# Rfid.net
KiCad netlist of a schematic drawn in EAGLE
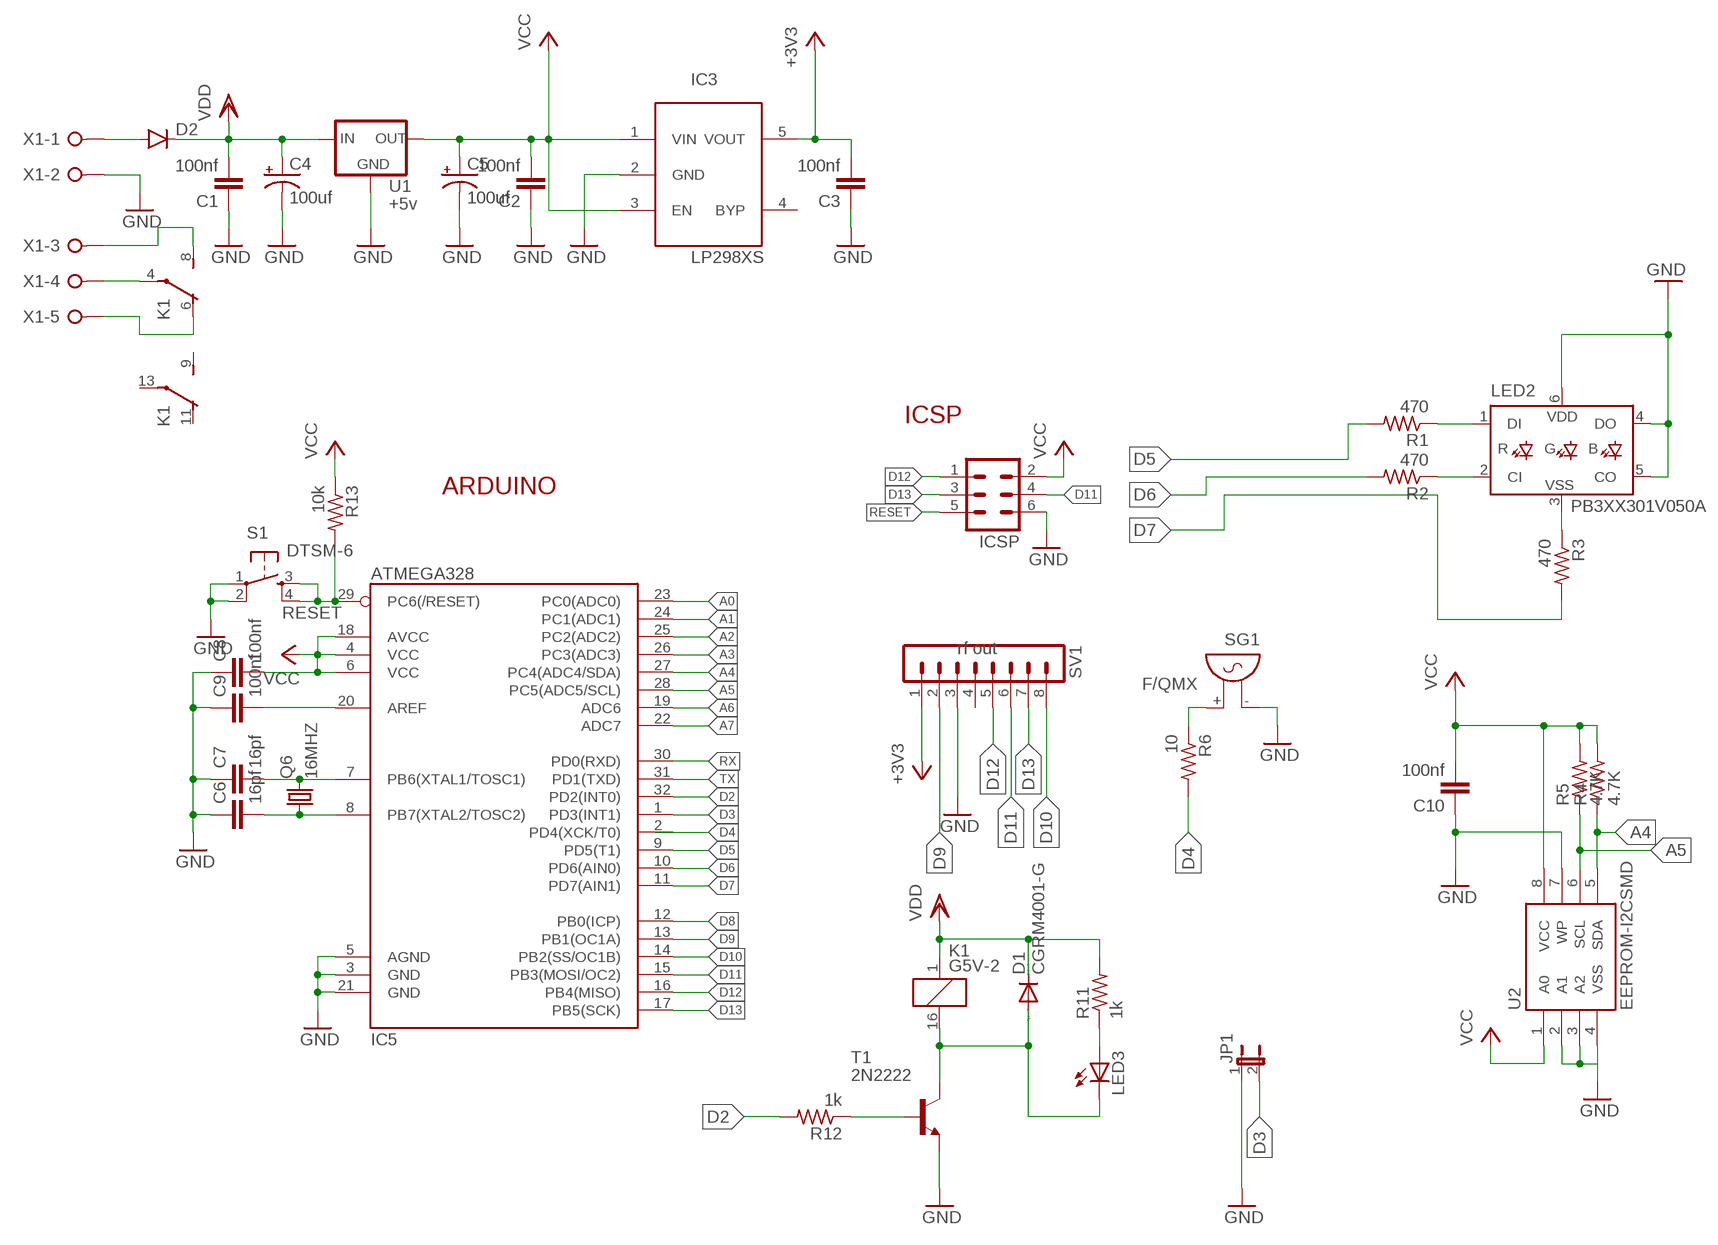
[diagram p0: schematic, sheet 1]

(export (version "E")
  (design (tool "Eeschema 10.0.6"))
  (components
    (comp (ref "C1")
      (value "100nf")
      (footprint "eagle-import:C0805")
      (libsource (lib "eagle-import") (part "C-EUC0805"))
    )
    (comp (ref "C2")
      (value "100nf")
      (footprint "eagle-import:C0805")
      (libsource (lib "eagle-import") (part "C-EUC0805"))
    )
    (comp (ref "C3")
      (value "100nf")
      (footprint "eagle-import:C0805")
      (libsource (lib "eagle-import") (part "C-EUC0805"))
    )
    (comp (ref "C4")
      (value "100uf")
      (footprint "eagle-import:PANASONIC_D")
      (libsource (lib "eagle-import") (part "CAP_POLD"))
    )
    (comp (ref "C5")
      (value "100uf")
      (footprint "eagle-import:PANASONIC_D")
      (libsource (lib "eagle-import") (part "CAP_POLD"))
    )
    (comp (ref "C6")
      (value "16pf")
      (footprint "eagle-import:C0805")
      (libsource (lib "eagle-import") (part "C-EUC0805"))
    )
    (comp (ref "C7")
      (value "16pf")
      (footprint "eagle-import:C0805")
      (libsource (lib "eagle-import") (part "C-EUC0805"))
    )
    (comp (ref "C8")
      (value "100nf")
      (footprint "eagle-import:C0805")
      (libsource (lib "eagle-import") (part "C-EUC0805"))
    )
    (comp (ref "C9")
      (value "100nf")
      (footprint "eagle-import:C0805")
      (libsource (lib "eagle-import") (part "C-EUC0805"))
    )
    (comp (ref "C10")
      (value "100nf")
      (footprint "eagle-import:C0805")
      (libsource (lib "eagle-import") (part "C-EUC0805"))
    )
    (comp (ref "D1")
      (value "CGRM4001-G")
      (footprint "eagle-import:SOD-123_MINI-SMA")
      (libsource (lib "eagle-import") (part "CGRM400-G1"))
    )
    (comp (ref "D2")
      (value "DIODESMA-ALT")
      (footprint "eagle-import:SMA-DIODE_ALT")
      (libsource (lib "eagle-import") (part "DIODESMA-ALT"))
    )
    (comp (ref "IC3")
      (value "LP298XS")
      (footprint "eagle-import:SOT23-5L")
      (libsource (lib "eagle-import") (part "LP298XS"))
    )
    (comp (ref "IC5")
      (value "ATMEGA328")
      (footprint "eagle-import:TQFP32-08")
      (libsource (lib "eagle-import") (part "ATMEGA168"))
    )
    (comp (ref "ICSP")
      (value "ML6")
      (footprint "eagle-import:ML6")
      (libsource (lib "eagle-import") (part "ML6"))
    )
    (comp (ref "JP1")
      (value "JUMPER-2PTH")
      (footprint "eagle-import:1X02")
      (libsource (lib "eagle-import") (part "JUMPER-2PTH"))
    )
    (comp (ref "K1")
      (value "G5V-2")
      (footprint "eagle-import:G5V-2")
      (fields (field (name "MPN") "G5V-2 5DC"))
      (libsource (lib "eagle-import") (part "G5V-2"))
    )
    (comp (ref "LED2")
      (value "PB3XX301V050A")
      (footprint "eagle-import:PB3XX301V050A")
      (libsource (lib "eagle-import") (part "PB3XX301V050A"))
    )
    (comp (ref "LED3")
      (value "LEDCHIPLED_0805")
      (footprint "eagle-import:CHIPLED_0805")
      (libsource (lib "eagle-import") (part "LEDCHIPLED_0805"))
    )
    (comp (ref "Q6")
      (value "16MHZ")
      (footprint "eagle-import:HC49_S")
      (libsource (lib "eagle-import") (part "CRYSTALHC49S"))
    )
    (comp (ref "R1")
      (value "470")
      (footprint "eagle-import:R0805")
      (libsource (lib "eagle-import") (part "R-US_R0805"))
    )
    (comp (ref "R2")
      (value "470")
      (footprint "eagle-import:R0805")
      (libsource (lib "eagle-import") (part "R-US_R0805"))
    )
    (comp (ref "R3")
      (value "470")
      (footprint "eagle-import:R0805")
      (libsource (lib "eagle-import") (part "R-US_R0805"))
    )
    (comp (ref "R4")
      (value "4.7K")
      (footprint "eagle-import:R0805")
      (libsource (lib "eagle-import") (part "R-US_R0805"))
    )
    (comp (ref "R5")
      (value "4.7K")
      (footprint "eagle-import:R0805")
      (libsource (lib "eagle-import") (part "R-US_R0805"))
    )
    (comp (ref "R6")
      (value "10")
      (footprint "eagle-import:R0805")
      (libsource (lib "eagle-import") (part "R-US_R0805"))
    )
    (comp (ref "R11")
      (value "1k")
      (footprint "eagle-import:R0805")
      (libsource (lib "eagle-import") (part "R-US_R0805"))
    )
    (comp (ref "R12")
      (value "1k")
      (footprint "eagle-import:R0805")
      (libsource (lib "eagle-import") (part "R-US_R0805"))
    )
    (comp (ref "R13")
      (value "10k")
      (footprint "eagle-import:R0805")
      (libsource (lib "eagle-import") (part "R-US_R0805"))
    )
    (comp (ref "S1")
      (value "DTSM-6")
      (footprint "eagle-import:DTSM-6")
      (libsource (lib "eagle-import") (part "DTSM-6"))
    )
    (comp (ref "SG1")
      (value "F/QMX")
      (footprint "eagle-import:F_QMX")
      (libsource (lib "eagle-import") (part "F/QMX"))
    )
    (comp (ref "SV1")
      (value "MA08-1")
      (footprint "eagle-import:MA08-1")
      (libsource (lib "eagle-import") (part "MA08-1"))
    )
    (comp (ref "T1")
      (value "2N2222")
      (footprint "eagle-import:SOT23-BEC")
      (libsource (lib "eagle-import") (part "-NPN-SOT23-BECMMBT2222ALT1"))
    )
    (comp (ref "U1")
      (value "+5v")
      (footprint "eagle-import:TO-252")
      (libsource (lib "eagle-import") (part "V_REG_78XX7812"))
    )
    (comp (ref "U2")
      (value "EEPROM-I2CSMD")
      (footprint "eagle-import:SO08")
      (libsource (lib "eagle-import") (part "EEPROM-I2CSMD"))
    )
    (comp (ref "X1")
      (value "W237-05P")
      (footprint "eagle-import:W237-5P")
      (libsource (lib "eagle-import") (part "W237-05P"))
    )
  )
  (nets
    (net (code "1") (name "+3V3") (class "Default")
      (node (ref "C3") (pin "2") (pinfunction "2_2") (pintype "passive"))
      (node (ref "IC3") (pin "5") (pinfunction "VOUT_5") (pintype "bidirectional"))
      (node (ref "SV1") (pin "1") (pinfunction "1_1") (pintype "passive"))
    )
    (net (code "2") (name "A0") (class "Default")
      (node (ref "IC5") (pin "23") (pinfunction "PC0(ADC0)_23") (pintype "bidirectional"))
    )
    (net (code "3") (name "A1") (class "Default")
      (node (ref "IC5") (pin "24") (pinfunction "PC1(ADC1)_24") (pintype "bidirectional"))
    )
    (net (code "4") (name "A2") (class "Default")
      (node (ref "IC5") (pin "25") (pinfunction "PC2(ADC2)_25") (pintype "bidirectional"))
    )
    (net (code "5") (name "A3") (class "Default")
      (node (ref "IC5") (pin "26") (pinfunction "PC3(ADC3)_26") (pintype "bidirectional"))
    )
    (net (code "6") (name "A4") (class "Default")
      (node (ref "IC5") (pin "27") (pinfunction "PC4(ADC4/SDA)_27") (pintype "bidirectional"))
      (node (ref "R4") (pin "1") (pinfunction "1_1") (pintype "passive"))
      (node (ref "U2") (pin "5") (pinfunction "SDA_5") (pintype "bidirectional"))
    )
    (net (code "7") (name "A5") (class "Default")
      (node (ref "IC5") (pin "28") (pinfunction "PC5(ADC5/SCL)_28") (pintype "bidirectional"))
      (node (ref "R5") (pin "1") (pinfunction "1_1") (pintype "passive"))
      (node (ref "U2") (pin "6") (pinfunction "SCL_6") (pintype "bidirectional"))
    )
    (net (code "8") (name "A6") (class "Default")
      (node (ref "IC5") (pin "19") (pinfunction "ADC6_19") (pintype "bidirectional"))
    )
    (net (code "9") (name "A7") (class "Default")
      (node (ref "IC5") (pin "22") (pinfunction "ADC7_22") (pintype "bidirectional"))
    )
    (net (code "10") (name "D2") (class "Default")
      (node (ref "IC5") (pin "32") (pinfunction "PD2(INT0)_32") (pintype "bidirectional"))
      (node (ref "R12") (pin "2") (pinfunction "2_2") (pintype "passive"))
    )
    (net (code "11") (name "D3") (class "Default")
      (node (ref "IC5") (pin "1") (pinfunction "PD3(INT1)_1") (pintype "bidirectional"))
      (node (ref "JP1") (pin "2") (pinfunction "2_2") (pintype "passive"))
    )
    (net (code "12") (name "D4") (class "Default")
      (node (ref "IC5") (pin "2") (pinfunction "PD4(XCK/T0)_2") (pintype "bidirectional"))
      (node (ref "R6") (pin "2") (pinfunction "2_2") (pintype "passive"))
    )
    (net (code "13") (name "D5") (class "Default")
      (node (ref "IC5") (pin "9") (pinfunction "PD5(T1)_9") (pintype "bidirectional"))
      (node (ref "R1") (pin "2") (pinfunction "2_2") (pintype "passive"))
    )
    (net (code "14") (name "D6") (class "Default")
      (node (ref "IC5") (pin "10") (pinfunction "PD6(AIN0)_10") (pintype "bidirectional"))
      (node (ref "R2") (pin "2") (pinfunction "2_2") (pintype "passive"))
    )
    (net (code "15") (name "D7") (class "Default")
      (node (ref "IC5") (pin "11") (pinfunction "PD7(AIN1)_11") (pintype "bidirectional"))
      (node (ref "R3") (pin "2") (pinfunction "2_2") (pintype "passive"))
    )
    (net (code "16") (name "D8") (class "Default")
      (node (ref "IC5") (pin "12") (pinfunction "PB0(ICP)_12") (pintype "bidirectional"))
    )
    (net (code "17") (name "D9") (class "Default")
      (node (ref "IC5") (pin "13") (pinfunction "PB1(OC1A)_13") (pintype "bidirectional"))
      (node (ref "SV1") (pin "2") (pinfunction "2_2") (pintype "passive"))
    )
    (net (code "18") (name "D10") (class "Default")
      (node (ref "IC5") (pin "14") (pinfunction "PB2(SS/OC1B)_14") (pintype "bidirectional"))
      (node (ref "SV1") (pin "8") (pinfunction "8_8") (pintype "passive"))
    )
    (net (code "19") (name "D11") (class "Default")
      (node (ref "IC5") (pin "15") (pinfunction "PB3(MOSI/OC2)_15") (pintype "bidirectional"))
      (node (ref "ICSP") (pin "4") (pinfunction "4_4") (pintype "passive"))
      (node (ref "SV1") (pin "6") (pinfunction "6_6") (pintype "passive"))
    )
    (net (code "20") (name "D12") (class "Default")
      (node (ref "IC5") (pin "16") (pinfunction "PB4(MISO)_16") (pintype "bidirectional"))
      (node (ref "ICSP") (pin "1") (pinfunction "1_1") (pintype "passive"))
      (node (ref "SV1") (pin "5") (pinfunction "5_5") (pintype "passive"))
    )
    (net (code "21") (name "D13") (class "Default")
      (node (ref "IC5") (pin "17") (pinfunction "PB5(SCK)_17") (pintype "bidirectional"))
      (node (ref "ICSP") (pin "3") (pinfunction "3_3") (pintype "passive"))
      (node (ref "SV1") (pin "7") (pinfunction "7_7") (pintype "passive"))
    )
    (net (code "22") (name "GND") (class "Default")
      (node (ref "C1") (pin "1") (pinfunction "1_1") (pintype "passive"))
      (node (ref "C10") (pin "1") (pinfunction "1_1") (pintype "passive"))
      (node (ref "C2") (pin "1") (pinfunction "1_1") (pintype "passive"))
      (node (ref "C3") (pin "1") (pinfunction "1_1") (pintype "passive"))
      (node (ref "C4") (pin "-") (pinfunction "-_-") (pintype "passive"))
      (node (ref "C5") (pin "-") (pinfunction "-_-") (pintype "passive"))
      (node (ref "C6") (pin "1") (pinfunction "1_1") (pintype "passive"))
      (node (ref "C7") (pin "1") (pinfunction "1_1") (pintype "passive"))
      (node (ref "C8") (pin "1") (pinfunction "1_1") (pintype "passive"))
      (node (ref "C9") (pin "1") (pinfunction "1_1") (pintype "passive"))
      (node (ref "IC3") (pin "2") (pinfunction "GND_2") (pintype "bidirectional"))
      (node (ref "IC5") (pin "21") (pinfunction "GND_21") (pintype "bidirectional"))
      (node (ref "IC5") (pin "3") (pinfunction "GND_3") (pintype "bidirectional"))
      (node (ref "IC5") (pin "5") (pinfunction "AGND_5") (pintype "bidirectional"))
      (node (ref "ICSP") (pin "6") (pinfunction "6_6") (pintype "passive"))
      (node (ref "JP1") (pin "1") (pinfunction "1_1") (pintype "passive"))
      (node (ref "LED2") (pin "4") (pinfunction "DO_4") (pintype "output"))
      (node (ref "LED2") (pin "5") (pinfunction "CO_5") (pintype "output"))
      (node (ref "LED2") (pin "6") (pinfunction "VDD_6") (pintype "power_in"))
      (node (ref "S1") (pin "1") (pinfunction "1_1") (pintype "passive"))
      (node (ref "S1") (pin "2") (pinfunction "2_2") (pintype "passive"))
      (node (ref "SG1") (pin "-") (pinfunction "1_-") (pintype "passive"))
      (node (ref "SV1") (pin "3") (pinfunction "3_3") (pintype "passive"))
      (node (ref "T1") (pin "E") (pinfunction "E_E") (pintype "passive"))
      (node (ref "U1") (pin "3") (pinfunction "GND_3") (pintype "input"))
      (node (ref "U2") (pin "2") (pinfunction "A1_2") (pintype "bidirectional"))
      (node (ref "U2") (pin "3") (pinfunction "A2_3") (pintype "bidirectional"))
      (node (ref "U2") (pin "4") (pinfunction "VSS_4") (pintype "power_in"))
      (node (ref "U2") (pin "7") (pinfunction "WP_7") (pintype "bidirectional"))
      (node (ref "X1") (pin "2") (pinfunction "KL_2") (pintype "passive"))
    )
    (net (code "23") (name "Net-(IC5-AREF)") (class "Default")
      (node (ref "C9") (pin "2") (pinfunction "2_2") (pintype "passive"))
      (node (ref "IC5") (pin "20") (pinfunction "AREF_20") (pintype "bidirectional"))
    )
    (net (code "24") (name "Net-(IC5-PB6(XTAL1{slash}TOSC1))") (class "Default")
      (node (ref "C7") (pin "2") (pinfunction "2_2") (pintype "passive"))
      (node (ref "IC5") (pin "7") (pinfunction "PB6(XTAL1/TOSC1)_7") (pintype "bidirectional"))
      (node (ref "Q6") (pin "2") (pinfunction "2_2") (pintype "passive"))
    )
    (net (code "25") (name "Net-(IC5-PB7(XTAL2{slash}TOSC2))") (class "Default")
      (node (ref "C6") (pin "2") (pinfunction "2_2") (pintype "passive"))
      (node (ref "IC5") (pin "8") (pinfunction "PB7(XTAL2/TOSC2)_8") (pintype "bidirectional"))
      (node (ref "Q6") (pin "1") (pinfunction "1_1") (pintype "passive"))
    )
    (net (code "26") (name "Net-(K1A-O)") (class "Default")
      (node (ref "K1") (pin "6") (pinfunction "O_6") (pintype "passive"))
      (node (ref "X1") (pin "5") (pinfunction "KL_5") (pintype "passive"))
    )
    (net (code "27") (name "Net-(K1A-P)") (class "Default")
      (node (ref "K1") (pin "4") (pinfunction "P_4") (pintype "passive"))
      (node (ref "X1") (pin "4") (pinfunction "KL_4") (pintype "passive"))
    )
    (net (code "28") (name "Net-(K1A-S)") (class "Default")
      (node (ref "K1") (pin "8") (pinfunction "S_8") (pintype "passive"))
      (node (ref "X1") (pin "3") (pinfunction "KL_3") (pintype "passive"))
    )
    (net (code "29") (name "Net-(K1C-2)") (class "Default")
      (node (ref "D1") (pin "A") (pinfunction "A_A") (pintype "passive"))
      (node (ref "K1") (pin "16") (pinfunction "2_16") (pintype "passive"))
      (node (ref "LED3") (pin "C") (pinfunction "C_C") (pintype "passive"))
      (node (ref "T1") (pin "C") (pinfunction "C_C") (pintype "passive"))
    )
    (net (code "30") (name "Net-(LED2-CI)") (class "Default")
      (node (ref "LED2") (pin "2") (pinfunction "CI_2") (pintype "input"))
      (node (ref "R2") (pin "1") (pinfunction "1_1") (pintype "passive"))
    )
    (net (code "31") (name "Net-(LED2-DI)") (class "Default")
      (node (ref "LED2") (pin "1") (pinfunction "DI_1") (pintype "input"))
      (node (ref "R1") (pin "1") (pinfunction "1_1") (pintype "passive"))
    )
    (net (code "32") (name "Net-(LED2-VSS)") (class "Default")
      (node (ref "LED2") (pin "3") (pinfunction "VSS_3") (pintype "power_in"))
      (node (ref "R3") (pin "1") (pinfunction "1_1") (pintype "passive"))
    )
    (net (code "33") (name "Net-(LED3-PadA)") (class "Default")
      (node (ref "LED3") (pin "A") (pinfunction "A_A") (pintype "passive"))
      (node (ref "R11") (pin "1") (pinfunction "1_1") (pintype "passive"))
    )
    (net (code "34") (name "Net-(R12-Pad1)") (class "Default")
      (node (ref "R12") (pin "1") (pinfunction "1_1") (pintype "passive"))
      (node (ref "T1") (pin "B") (pinfunction "B_B") (pintype "passive"))
    )
    (net (code "35") (name "Net-(SG1-2)") (class "Default")
      (node (ref "R6") (pin "1") (pinfunction "1_1") (pintype "passive"))
      (node (ref "SG1") (pin "+") (pinfunction "2_+") (pintype "passive"))
    )
    (net (code "36") (name "Net-(X1A-KL)") (class "Default")
      (node (ref "D2") (pin "A") (pinfunction "A_A") (pintype "passive"))
      (node (ref "X1") (pin "1") (pinfunction "KL_1") (pintype "passive"))
    )
    (net (code "37") (name "RESET") (class "Default")
      (node (ref "IC5") (pin "29") (pinfunction "PC6(/RESET)_29") (pintype "bidirectional"))
      (node (ref "ICSP") (pin "5") (pinfunction "5_5") (pintype "passive"))
      (node (ref "R13") (pin "2") (pinfunction "2_2") (pintype "passive"))
      (node (ref "S1") (pin "3") (pinfunction "3_3") (pintype "passive"))
      (node (ref "S1") (pin "4") (pinfunction "4_4") (pintype "passive"))
    )
    (net (code "38") (name "RX") (class "Default")
      (node (ref "IC5") (pin "30") (pinfunction "PD0(RXD)_30") (pintype "bidirectional"))
    )
    (net (code "39") (name "TX") (class "Default")
      (node (ref "IC5") (pin "31") (pinfunction "PD1(TXD)_31") (pintype "bidirectional"))
    )
    (net (code "40") (name "VCC") (class "Default")
      (node (ref "C10") (pin "2") (pinfunction "2_2") (pintype "passive"))
      (node (ref "C2") (pin "2") (pinfunction "2_2") (pintype "passive"))
      (node (ref "C5") (pin "+") (pinfunction "+_+") (pintype "passive"))
      (node (ref "C8") (pin "2") (pinfunction "2_2") (pintype "passive"))
      (node (ref "IC3") (pin "1") (pinfunction "VIN_1") (pintype "bidirectional"))
      (node (ref "IC3") (pin "3") (pinfunction "EN_3") (pintype "bidirectional"))
      (node (ref "IC5") (pin "18") (pinfunction "AVCC_18") (pintype "bidirectional"))
      (node (ref "IC5") (pin "4") (pinfunction "VCC_4") (pintype "bidirectional"))
      (node (ref "IC5") (pin "6") (pinfunction "VCC_6") (pintype "bidirectional"))
      (node (ref "ICSP") (pin "2") (pinfunction "2_2") (pintype "passive"))
      (node (ref "R13") (pin "1") (pinfunction "1_1") (pintype "passive"))
      (node (ref "R4") (pin "2") (pinfunction "2_2") (pintype "passive"))
      (node (ref "R5") (pin "2") (pinfunction "2_2") (pintype "passive"))
      (node (ref "U1") (pin "2") (pinfunction "OUT_2") (pintype "passive"))
      (node (ref "U2") (pin "1") (pinfunction "A0_1") (pintype "bidirectional"))
      (node (ref "U2") (pin "8") (pinfunction "VCC_8") (pintype "power_in"))
    )
    (net (code "41") (name "VDD") (class "Default")
      (node (ref "C1") (pin "2") (pinfunction "2_2") (pintype "passive"))
      (node (ref "C4") (pin "+") (pinfunction "+_+") (pintype "passive"))
      (node (ref "D1") (pin "C") (pinfunction "C_C") (pintype "passive"))
      (node (ref "D2") (pin "C") (pinfunction "C_C") (pintype "passive"))
      (node (ref "K1") (pin "1") (pinfunction "1_1") (pintype "passive"))
      (node (ref "R11") (pin "2") (pinfunction "2_2") (pintype "passive"))
      (node (ref "U1") (pin "1") (pinfunction "IN_1") (pintype "input"))
    )
    (net (code "42") (name "unconnected-(IC3-BYP-Pad4)") (class "Default")
      (node (ref "IC3") (pin "4") (pinfunction "BYP_4") (pintype "bidirectional"))
    )
    (net (code "43") (name "unconnected-(K1B-O-Pad11)") (class "Default")
      (node (ref "K1") (pin "11") (pinfunction "O_11") (pintype "passive"))
    )
    (net (code "44") (name "unconnected-(K1B-P-Pad13)") (class "Default")
      (node (ref "K1") (pin "13") (pinfunction "P_13") (pintype "passive"))
    )
    (net (code "45") (name "unconnected-(K1B-S-Pad9)") (class "Default")
      (node (ref "K1") (pin "9") (pinfunction "S_9") (pintype "passive"))
    )
    (net (code "46") (name "unconnected-(SV1-Pad4)") (class "Default")
      (node (ref "SV1") (pin "4") (pinfunction "4_4") (pintype "passive"))
    )
  )
)
